# TI_POW.net
KiCad netlist of a schematic drawn in Altium Designer
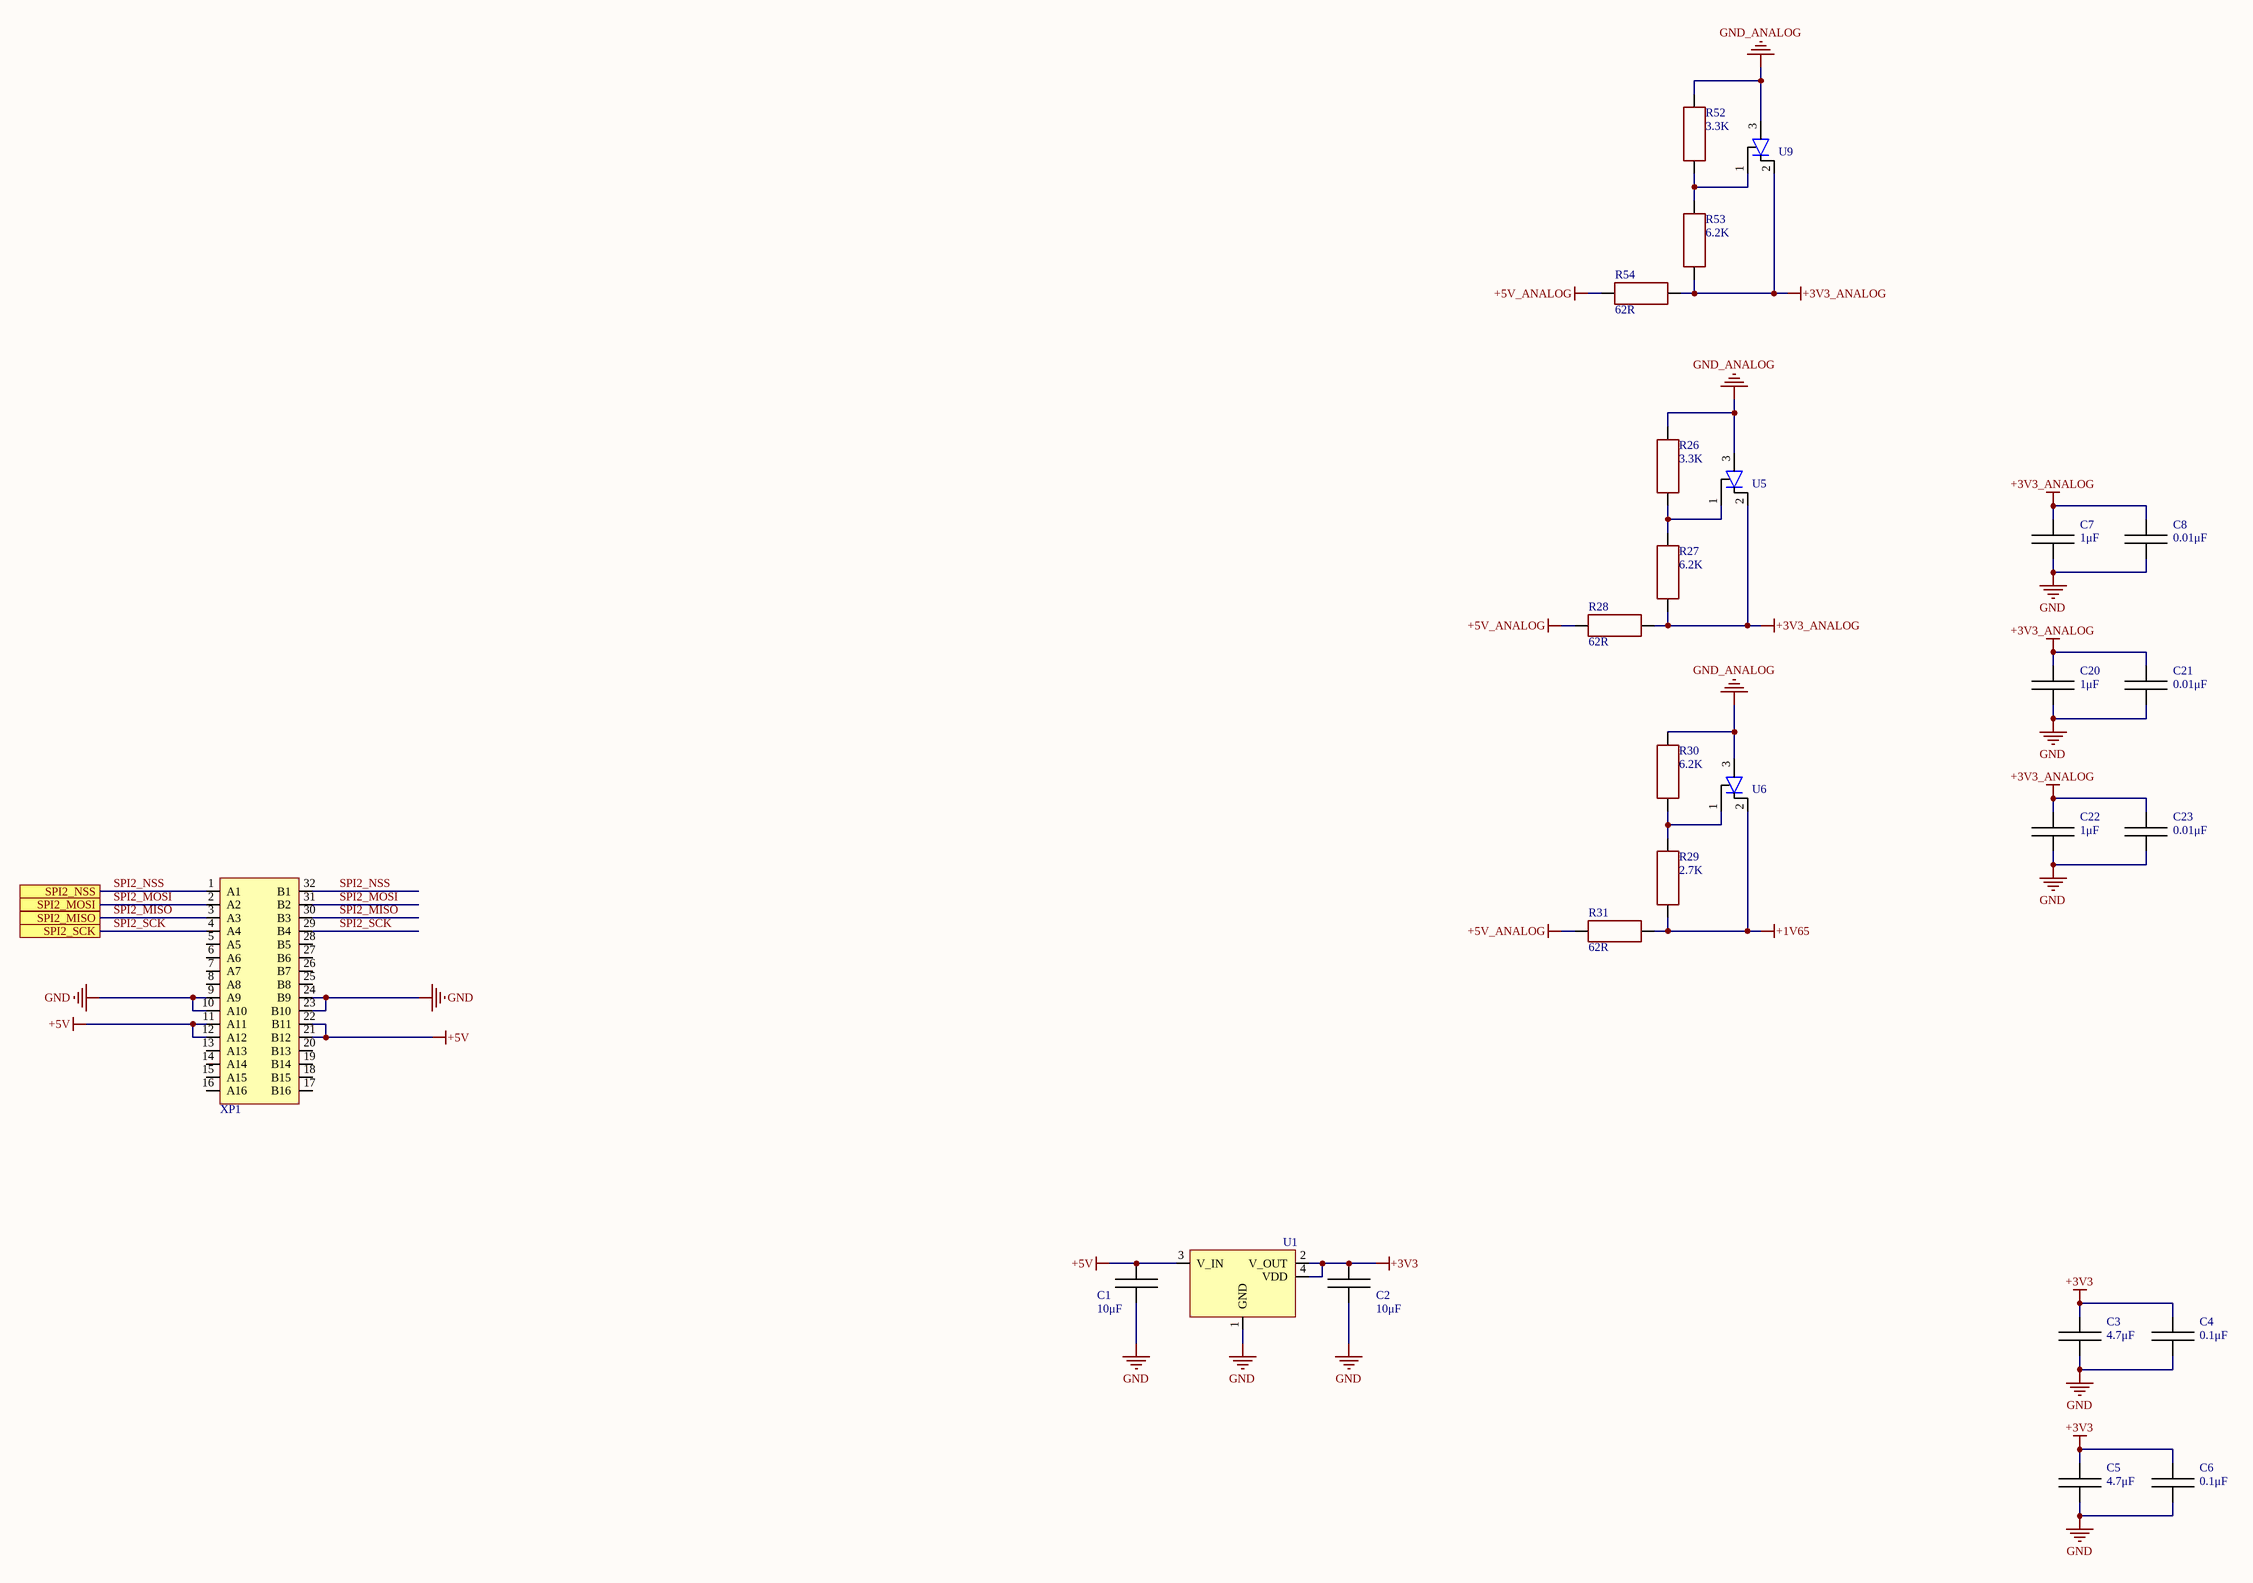
[diagram p0: TI_POW.SchDoc]

(export (version "E")
  (design (tool "Eeschema 10.0.6"))
  (components
    (comp (ref "C1")
      (value "10μF")
      (footprint "CAP: 2220")
      (fields (field (name "VOLTAGE") "16V") (field (name "Comment") "Cap_2220"))
      (libsource (lib "capacitor") (part "Cap_2220"))
    )
    (comp (ref "C2")
      (value "10μF")
      (footprint "CAP: 2220")
      (fields (field (name "VOLTAGE") "16V") (field (name "Comment") "Cap_2220"))
      (libsource (lib "capacitor") (part "Cap_2220"))
    )
    (comp (ref "C3")
      (value "4.7μF")
      (footprint "CAP: 0603")
      (fields (field (name "VOLTAGE") "25V") (field (name "Comment") "Cap_0603"))
      (libsource (lib "capacitor") (part "Cap_0603"))
    )
    (comp (ref "C4")
      (value "0.1μF")
      (footprint "CAP: 0603")
      (fields (field (name "VOLTAGE") "16V") (field (name "Comment") "Cap_0603"))
      (libsource (lib "capacitor") (part "Cap_0603"))
    )
    (comp (ref "C5")
      (value "4.7μF")
      (footprint "CAP: 0603")
      (fields (field (name "VOLTAGE") "25V") (field (name "Comment") "Cap_0603"))
      (libsource (lib "capacitor") (part "Cap_0603"))
    )
    (comp (ref "C6")
      (value "0.1μF")
      (footprint "CAP: 0603")
      (fields (field (name "VOLTAGE") "16V") (field (name "Comment") "Cap_0603"))
      (libsource (lib "capacitor") (part "Cap_0603"))
    )
    (comp (ref "C7")
      (value "1μF")
      (footprint "CAP: 0603")
      (fields (field (name "VOLTAGE") "16V") (field (name "Comment") "Cap_0603"))
      (libsource (lib "capacitor") (part "Cap_0603"))
    )
    (comp (ref "C8")
      (value "0.01μF")
      (footprint "CAP: 0603")
      (fields (field (name "VOLTAGE") "50V") (field (name "Comment") "Cap_0603"))
      (libsource (lib "capacitor") (part "Cap_0603"))
    )
    (comp (ref "C20")
      (value "1μF")
      (footprint "CAP: 0603")
      (fields (field (name "VOLTAGE") "16V") (field (name "Comment") "Cap_0603"))
      (libsource (lib "capacitor") (part "Cap_0603"))
    )
    (comp (ref "C21")
      (value "0.01μF")
      (footprint "CAP: 0603")
      (fields (field (name "VOLTAGE") "50V") (field (name "Comment") "Cap_0603"))
      (libsource (lib "capacitor") (part "Cap_0603"))
    )
    (comp (ref "C22")
      (value "1μF")
      (footprint "CAP: 0603")
      (fields (field (name "VOLTAGE") "16V") (field (name "Comment") "Cap_0603"))
      (libsource (lib "capacitor") (part "Cap_0603"))
    )
    (comp (ref "C23")
      (value "0.01μF")
      (footprint "CAP: 0603")
      (fields (field (name "VOLTAGE") "50V") (field (name "Comment") "Cap_0603"))
      (libsource (lib "capacitor") (part "Cap_0603"))
    )
    (comp (ref "R26")
      (value "3.3K")
      (footprint "RES: 0603")
      (fields
        (field (name "POWER") "0.1W")
        (field (name "TOLERANCE") "±5%")
        (field (name "Comment") "Resistor_0603")
      )
      (libsource (lib "resistor") (part "Resistor_0603"))
    )
    (comp (ref "R27")
      (value "6.2K")
      (footprint "RES: 0603")
      (fields
        (field (name "POWER") "0.1W")
        (field (name "TOLERANCE") "±5%")
        (field (name "Comment") "Resistor_0603")
      )
      (libsource (lib "resistor") (part "Resistor_0603"))
    )
    (comp (ref "R28")
      (value "62R")
      (footprint "RES: 0603")
      (fields
        (field (name "POWER") "0.1W")
        (field (name "TOLERANCE") "±5%")
        (field (name "Comment") "Resistor_0603")
      )
      (libsource (lib "") (part "Resistor_0603_1"))
    )
    (comp (ref "R29")
      (value "2.7K")
      (footprint "RES: 0603")
      (fields
        (field (name "POWER") "0.1W")
        (field (name "TOLERANCE") "±5%")
        (field (name "Comment") "Resistor_0603")
      )
      (libsource (lib "resistor") (part "Resistor_0603"))
    )
    (comp (ref "R30")
      (value "6.2K")
      (footprint "RES: 0603")
      (fields
        (field (name "POWER") "0.1W")
        (field (name "TOLERANCE") "±5%")
        (field (name "Comment") "Resistor_0603")
      )
      (libsource (lib "resistor") (part "Resistor_0603"))
    )
    (comp (ref "R31")
      (value "62R")
      (footprint "RES: 0603")
      (fields
        (field (name "POWER") "0.1W")
        (field (name "TOLERANCE") "±5%")
        (field (name "Comment") "Resistor_0603")
      )
      (libsource (lib "") (part "Resistor_0603_1"))
    )
    (comp (ref "R52")
      (value "3.3K")
      (footprint "RES: 0603")
      (fields
        (field (name "POWER") "0.1W")
        (field (name "TOLERANCE") "±5%")
        (field (name "Comment") "Resistor_0603")
      )
      (libsource (lib "resistor") (part "Resistor_0603"))
    )
    (comp (ref "R53")
      (value "6.2K")
      (footprint "RES: 0603")
      (fields
        (field (name "POWER") "0.1W")
        (field (name "TOLERANCE") "±5%")
        (field (name "Comment") "Resistor_0603")
      )
      (libsource (lib "resistor") (part "Resistor_0603"))
    )
    (comp (ref "R54")
      (value "62R")
      (footprint "RES: 0603")
      (fields
        (field (name "POWER") "0.1W")
        (field (name "TOLERANCE") "±5%")
        (field (name "Comment") "Resistor_0603")
      )
      (libsource (lib "") (part "Resistor_0603_1"))
    )
    (comp (ref "U1")
      (value "LD1117S33CTR4")
      (footprint "SOT-223-3")
      (description "LDO Voltage Regulator 3.3V 0.8A Positive")
      (fields (field (name "MANUFACTURER") "STMicroelectronics"))
      (libsource (lib "MY_INT_LIB") (part "LD1117S33CTR"))
    )
    (comp (ref "U5")
      (value "TLVH431BIL3T")
      (footprint "SOT-23-3")
      (description "Voltage References 1.24V to 18V Prog Shunt Ref 100uA 60mA")
      (fields (field (name "MANUFACTURER") "STMicroelectronics"))
      (libsource (lib "MY_INT_LIB") (part "TLVH431BIL3T"))
    )
    (comp (ref "U6")
      (value "TLVH431BIL3T")
      (footprint "SOT-23-3")
      (description "Voltage References 1.24V to 18V Prog Shunt Ref 100uA 60mA")
      (fields (field (name "MANUFACTURER") "STMicroelectronics"))
      (libsource (lib "MY_INT_LIB") (part "TLVH431BIL3T"))
    )
    (comp (ref "U9")
      (value "TLVH431BIL3T")
      (footprint "SOT-23-3")
      (description "Voltage References 1.24V to 18V Prog Shunt Ref 100uA 60mA")
      (fields (field (name "MANUFACTURER") "STMicroelectronics"))
      (libsource (lib "MY_INT_LIB") (part "TLVH431BIL3T"))
    )
    (comp (ref "XP1")
      (value "DS1118-32M-R23")
      (footprint "DS1118-32M-R23")
      (description "DIN 41612 Connector")
      (fields (field (name "MANUFACTURER") "Connfly"))
      (libsource (lib "MY_INT_LIB") (part "DS1118-32M-R23"))
    )
  )
  (nets
    (net (code "1") (name "+1V65") (class "Default")
      (node (ref "R29") (pin "1") (pinfunction "1_1") (pintype "passive"))
      (node (ref "R31") (pin "1") (pinfunction "1_1") (pintype "passive"))
      (node (ref "U6") (pin "2") (pintype "power_in"))
    )
    (net (code "2") (name "+3V3") (class "Default")
      (node (ref "C2") (pin "2") (pinfunction "2_2") (pintype "passive"))
      (node (ref "C3") (pin "2") (pinfunction "2_2") (pintype "passive"))
      (node (ref "C4") (pin "2") (pinfunction "2_2") (pintype "passive"))
      (node (ref "C5") (pin "2") (pinfunction "2_2") (pintype "passive"))
      (node (ref "C6") (pin "2") (pinfunction "2_2") (pintype "passive"))
      (node (ref "U1") (pin "2") (pinfunction "V_OUT_2") (pintype "power_in"))
      (node (ref "U1") (pin "4") (pinfunction "VDD_4") (pintype "power_in"))
    )
    (net (code "3") (name "+3V3_ANALOG") (class "Default")
      (node (ref "C20") (pin "2") (pinfunction "2_2") (pintype "passive"))
      (node (ref "C21") (pin "2") (pinfunction "2_2") (pintype "passive"))
      (node (ref "C22") (pin "2") (pinfunction "2_2") (pintype "passive"))
      (node (ref "C23") (pin "2") (pinfunction "2_2") (pintype "passive"))
      (node (ref "C7") (pin "2") (pinfunction "2_2") (pintype "passive"))
      (node (ref "C8") (pin "2") (pinfunction "2_2") (pintype "passive"))
      (node (ref "R27") (pin "1") (pinfunction "1_1") (pintype "passive"))
      (node (ref "R28") (pin "1") (pinfunction "1_1") (pintype "passive"))
      (node (ref "R53") (pin "1") (pinfunction "1_1") (pintype "passive"))
      (node (ref "R54") (pin "1") (pinfunction "1_1") (pintype "passive"))
      (node (ref "U5") (pin "2") (pintype "power_in"))
      (node (ref "U9") (pin "2") (pintype "power_in"))
    )
    (net (code "4") (name "+5V") (class "Default")
      (node (ref "C1") (pin "2") (pinfunction "2_2") (pintype "passive"))
      (node (ref "U1") (pin "3") (pinfunction "V_IN_3") (pintype "power_in"))
      (node (ref "XP1") (pin "11") (pinfunction "A11_11") (pintype "passive"))
      (node (ref "XP1") (pin "12") (pinfunction "A12_12") (pintype "passive"))
      (node (ref "XP1") (pin "21") (pinfunction "B12_21") (pintype "passive"))
      (node (ref "XP1") (pin "22") (pinfunction "B11_22") (pintype "passive"))
    )
    (net (code "5") (name "+5V_ANALOG") (class "Default")
      (node (ref "R28") (pin "2") (pinfunction "2_2") (pintype "passive"))
      (node (ref "R31") (pin "2") (pinfunction "2_2") (pintype "passive"))
      (node (ref "R54") (pin "2") (pinfunction "2_2") (pintype "passive"))
    )
    (net (code "6") (name "/SPI2_MISO") (class "Default")
      (node (ref "XP1") (pin "3") (pinfunction "A3_3") (pintype "passive"))
      (node (ref "XP1") (pin "30") (pinfunction "B3_30") (pintype "passive"))
    )
    (net (code "7") (name "/SPI2_MOSI") (class "Default")
      (node (ref "XP1") (pin "2") (pinfunction "A2_2") (pintype "passive"))
      (node (ref "XP1") (pin "31") (pinfunction "B2_31") (pintype "passive"))
    )
    (net (code "8") (name "/SPI2_NSS") (class "Default")
      (node (ref "XP1") (pin "1") (pinfunction "A1_1") (pintype "passive"))
      (node (ref "XP1") (pin "32") (pinfunction "B1_32") (pintype "passive"))
    )
    (net (code "9") (name "/SPI2_SCK") (class "Default")
      (node (ref "XP1") (pin "29") (pinfunction "B4_29") (pintype "passive"))
      (node (ref "XP1") (pin "4") (pinfunction "A4_4") (pintype "passive"))
    )
    (net (code "10") (name "GND") (class "Default")
      (node (ref "C1") (pin "1") (pinfunction "1_1") (pintype "passive"))
      (node (ref "C2") (pin "1") (pinfunction "1_1") (pintype "passive"))
      (node (ref "C20") (pin "1") (pinfunction "1_1") (pintype "passive"))
      (node (ref "C21") (pin "1") (pinfunction "1_1") (pintype "passive"))
      (node (ref "C22") (pin "1") (pinfunction "1_1") (pintype "passive"))
      (node (ref "C23") (pin "1") (pinfunction "1_1") (pintype "passive"))
      (node (ref "C3") (pin "1") (pinfunction "1_1") (pintype "passive"))
      (node (ref "C4") (pin "1") (pinfunction "1_1") (pintype "passive"))
      (node (ref "C5") (pin "1") (pinfunction "1_1") (pintype "passive"))
      (node (ref "C6") (pin "1") (pinfunction "1_1") (pintype "passive"))
      (node (ref "C7") (pin "1") (pinfunction "1_1") (pintype "passive"))
      (node (ref "C8") (pin "1") (pinfunction "1_1") (pintype "passive"))
      (node (ref "U1") (pin "1") (pinfunction "GND_1") (pintype "power_in"))
      (node (ref "XP1") (pin "10") (pinfunction "A10_10") (pintype "passive"))
      (node (ref "XP1") (pin "23") (pinfunction "B10_23") (pintype "passive"))
      (node (ref "XP1") (pin "24") (pinfunction "B9_24") (pintype "passive"))
      (node (ref "XP1") (pin "9") (pinfunction "A9_9") (pintype "passive"))
    )
    (net (code "11") (name "GND_ANALOG") (class "Default")
      (node (ref "R26") (pin "2") (pinfunction "2_2") (pintype "passive"))
      (node (ref "R30") (pin "2") (pinfunction "2_2") (pintype "passive"))
      (node (ref "R52") (pin "2") (pinfunction "2_2") (pintype "passive"))
      (node (ref "U5") (pin "3") (pintype "power_in"))
      (node (ref "U6") (pin "3") (pintype "power_in"))
      (node (ref "U9") (pin "3") (pintype "power_in"))
    )
    (net (code "12") (name "Net-(R26-Pad1)") (class "Default")
      (node (ref "R26") (pin "1") (pinfunction "1_1") (pintype "passive"))
      (node (ref "R27") (pin "2") (pinfunction "2_2") (pintype "passive"))
      (node (ref "U5") (pin "1") (pintype "power_in"))
    )
    (net (code "13") (name "Net-(R29-Pad2)") (class "Default")
      (node (ref "R29") (pin "2") (pinfunction "2_2") (pintype "passive"))
      (node (ref "R30") (pin "1") (pinfunction "1_1") (pintype "passive"))
      (node (ref "U6") (pin "1") (pintype "power_in"))
    )
    (net (code "14") (name "Net-(R52-Pad1)") (class "Default")
      (node (ref "R52") (pin "1") (pinfunction "1_1") (pintype "passive"))
      (node (ref "R53") (pin "2") (pinfunction "2_2") (pintype "passive"))
      (node (ref "U9") (pin "1") (pintype "power_in"))
    )
    (net (code "15") (name "unconnected-(XP1-A5-Pad5)") (class "Default")
      (node (ref "XP1") (pin "5") (pinfunction "A5_5") (pintype "passive"))
    )
    (net (code "16") (name "unconnected-(XP1-A6-Pad6)") (class "Default")
      (node (ref "XP1") (pin "6") (pinfunction "A6_6") (pintype "passive"))
    )
    (net (code "17") (name "unconnected-(XP1-A7-Pad7)") (class "Default")
      (node (ref "XP1") (pin "7") (pinfunction "A7_7") (pintype "passive"))
    )
    (net (code "18") (name "unconnected-(XP1-A8-Pad8)") (class "Default")
      (node (ref "XP1") (pin "8") (pinfunction "A8_8") (pintype "passive"))
    )
    (net (code "19") (name "unconnected-(XP1-A13-Pad13)") (class "Default")
      (node (ref "XP1") (pin "13") (pinfunction "A13_13") (pintype "passive"))
    )
    (net (code "20") (name "unconnected-(XP1-A14-Pad14)") (class "Default")
      (node (ref "XP1") (pin "14") (pinfunction "A14_14") (pintype "passive"))
    )
    (net (code "21") (name "unconnected-(XP1-A15-Pad15)") (class "Default")
      (node (ref "XP1") (pin "15") (pinfunction "A15_15") (pintype "passive"))
    )
    (net (code "22") (name "unconnected-(XP1-A16-Pad16)") (class "Default")
      (node (ref "XP1") (pin "16") (pinfunction "A16_16") (pintype "passive"))
    )
    (net (code "23") (name "unconnected-(XP1-B5-Pad28)") (class "Default")
      (node (ref "XP1") (pin "28") (pinfunction "B5_28") (pintype "passive"))
    )
    (net (code "24") (name "unconnected-(XP1-B6-Pad27)") (class "Default")
      (node (ref "XP1") (pin "27") (pinfunction "B6_27") (pintype "passive"))
    )
    (net (code "25") (name "unconnected-(XP1-B7-Pad26)") (class "Default")
      (node (ref "XP1") (pin "26") (pinfunction "B7_26") (pintype "passive"))
    )
    (net (code "26") (name "unconnected-(XP1-B8-Pad25)") (class "Default")
      (node (ref "XP1") (pin "25") (pinfunction "B8_25") (pintype "passive"))
    )
    (net (code "27") (name "unconnected-(XP1-B13-Pad20)") (class "Default")
      (node (ref "XP1") (pin "20") (pinfunction "B13_20") (pintype "passive"))
    )
    (net (code "28") (name "unconnected-(XP1-B14-Pad19)") (class "Default")
      (node (ref "XP1") (pin "19") (pinfunction "B14_19") (pintype "passive"))
    )
    (net (code "29") (name "unconnected-(XP1-B15-Pad18)") (class "Default")
      (node (ref "XP1") (pin "18") (pinfunction "B15_18") (pintype "passive"))
    )
    (net (code "30") (name "unconnected-(XP1-B16-Pad17)") (class "Default")
      (node (ref "XP1") (pin "17") (pinfunction "B16_17") (pintype "passive"))
    )
  )
)
